# untitled.net
KiCad netlist of a schematic drawn in EAGLE
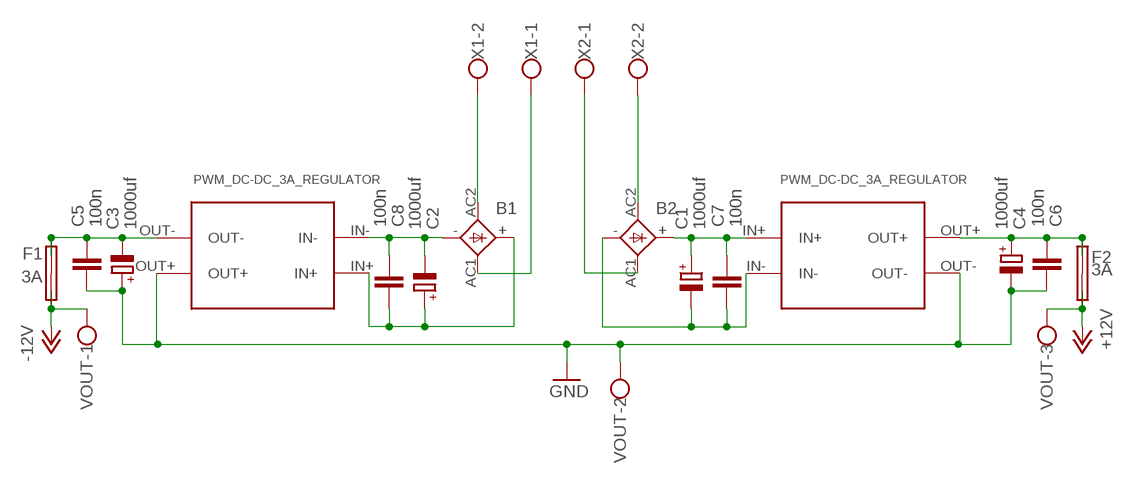
[diagram p0: schematic, sheet 1]
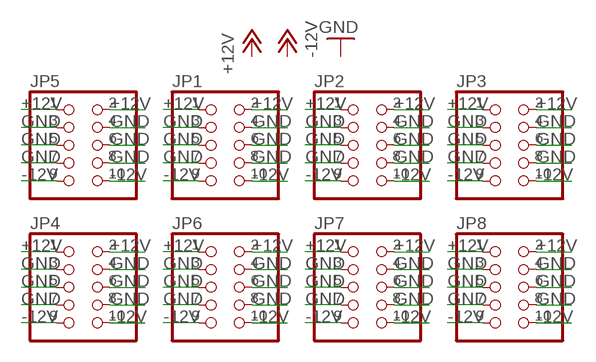
[diagram p1: schematic, sheet 2]

(export (version "E")
  (design (tool "Eeschema 10.0.6"))
  (components
    (comp (ref "B1")
      (value "FB15")
      (footprint "eagle-import:FB15")
      (libsource (lib "eagle-import") (part "FB15"))
    )
    (comp (ref "B2")
      (value "FB15")
      (footprint "eagle-import:FB15")
      (libsource (lib "eagle-import") (part "FB15"))
    )
    (comp (ref "C1")
      (value "1000uf")
      (footprint "eagle-import:TT5D11")
      (libsource (lib "eagle-import") (part "CPOL-EUTT5D11"))
    )
    (comp (ref "C2")
      (value "1000uf")
      (footprint "eagle-import:TT5D11")
      (libsource (lib "eagle-import") (part "CPOL-EUTT5D11"))
    )
    (comp (ref "C3")
      (value "1000uf")
      (footprint "eagle-import:TT5D11")
      (libsource (lib "eagle-import") (part "CPOL-EUTT5D11"))
    )
    (comp (ref "C4")
      (value "1000uf")
      (footprint "eagle-import:TT5D11")
      (libsource (lib "eagle-import") (part "CPOL-EUTT5D11"))
    )
    (comp (ref "C5")
      (value "100n")
      (footprint "eagle-import:C075-032X103")
      (libsource (lib "eagle-import") (part "C-EU075-032X103"))
    )
    (comp (ref "C6")
      (value "100n")
      (footprint "eagle-import:C075-032X103")
      (libsource (lib "eagle-import") (part "C-EU075-032X103"))
    )
    (comp (ref "C7")
      (value "100n")
      (footprint "eagle-import:C075-032X103")
      (libsource (lib "eagle-import") (part "C-EU075-032X103"))
    )
    (comp (ref "C8")
      (value "100n")
      (footprint "eagle-import:C075-032X103")
      (libsource (lib "eagle-import") (part "C-EU075-032X103"))
    )
    (comp (ref "F1")
      (value "3A")
      (footprint "eagle-import:SHK20L")
      (libsource (lib "eagle-import") (part "SHK20L"))
    )
    (comp (ref "F2")
      (value "3A")
      (footprint "eagle-import:SHK20L")
      (libsource (lib "eagle-import") (part "SHK20L"))
    )
    (comp (ref "PWM_DC-DC_3A_REGULATOR1")
      (value "CP8-ADJ")
      (footprint "eagle-import:CP8-ADJ")
      (libsource (lib "eagle-import") (part "CP8-ADJ"))
    )
    (comp (ref "PWM_DC-DC_3A_REGULATOR2")
      (value "CP8-ADJ")
      (footprint "eagle-import:CP8-ADJ")
      (libsource (lib "eagle-import") (part "CP8-ADJ"))
    )
    (comp (ref "VOUT")
      (value "W237-103")
      (footprint "eagle-import:W237-103")
      (fields (field (name "MPN") "237-103"))
      (libsource (lib "eagle-import") (part "W237-103"))
    )
    (comp (ref "X1")
      (value "W237-102")
      (footprint "eagle-import:W237-102")
      (fields (field (name "MPN") "237-102"))
      (libsource (lib "eagle-import") (part "W237-102"))
    )
    (comp (ref "X2")
      (value "W237-102")
      (footprint "eagle-import:W237-102")
      (fields (field (name "MPN") "237-102"))
      (libsource (lib "eagle-import") (part "W237-102"))
    )
    (comp (ref "JP1")
      (value "PINHD-2X5")
      (footprint "eagle-import:2X05")
      (libsource (lib "eagle-import") (part "PINHD-2X5"))
    )
    (comp (ref "JP2")
      (value "PINHD-2X5")
      (footprint "eagle-import:2X05")
      (libsource (lib "eagle-import") (part "PINHD-2X5"))
    )
    (comp (ref "JP3")
      (value "PINHD-2X5")
      (footprint "eagle-import:2X05")
      (libsource (lib "eagle-import") (part "PINHD-2X5"))
    )
    (comp (ref "JP4")
      (value "PINHD-2X5")
      (footprint "eagle-import:2X05")
      (libsource (lib "eagle-import") (part "PINHD-2X5"))
    )
    (comp (ref "JP5")
      (value "PINHD-2X5")
      (footprint "eagle-import:2X05")
      (libsource (lib "eagle-import") (part "PINHD-2X5"))
    )
    (comp (ref "JP6")
      (value "PINHD-2X5")
      (footprint "eagle-import:2X05")
      (libsource (lib "eagle-import") (part "PINHD-2X5"))
    )
    (comp (ref "JP7")
      (value "PINHD-2X5")
      (footprint "eagle-import:2X05")
      (libsource (lib "eagle-import") (part "PINHD-2X5"))
    )
    (comp (ref "JP8")
      (value "PINHD-2X5")
      (footprint "eagle-import:2X05")
      (libsource (lib "eagle-import") (part "PINHD-2X5"))
    )
  )
  (nets
    (net (code "1") (name "+12V") (class "Default")
      (node (ref "F2") (pin "1A") (pinfunction "1A_1A") (pintype "passive"))
      (node (ref "F2") (pin "1B") (pinfunction "1B_1B") (pintype "passive"))
      (node (ref "JP1") (pin "1") (pinfunction "1_1") (pintype "passive"))
      (node (ref "JP1") (pin "2") (pinfunction "2_2") (pintype "passive"))
      (node (ref "JP2") (pin "1") (pinfunction "1_1") (pintype "passive"))
      (node (ref "JP2") (pin "2") (pinfunction "2_2") (pintype "passive"))
      (node (ref "JP3") (pin "1") (pinfunction "1_1") (pintype "passive"))
      (node (ref "JP3") (pin "2") (pinfunction "2_2") (pintype "passive"))
      (node (ref "JP4") (pin "1") (pinfunction "1_1") (pintype "passive"))
      (node (ref "JP4") (pin "2") (pinfunction "2_2") (pintype "passive"))
      (node (ref "JP5") (pin "1") (pinfunction "1_1") (pintype "passive"))
      (node (ref "JP5") (pin "2") (pinfunction "2_2") (pintype "passive"))
      (node (ref "JP6") (pin "1") (pinfunction "1_1") (pintype "passive"))
      (node (ref "JP6") (pin "2") (pinfunction "2_2") (pintype "passive"))
      (node (ref "JP7") (pin "1") (pinfunction "1_1") (pintype "passive"))
      (node (ref "JP7") (pin "2") (pinfunction "2_2") (pintype "passive"))
      (node (ref "JP8") (pin "1") (pinfunction "1_1") (pintype "passive"))
      (node (ref "JP8") (pin "2") (pinfunction "2_2") (pintype "passive"))
      (node (ref "VOUT") (pin "3") (pinfunction "KL_3") (pintype "passive"))
    )
    (net (code "2") (name "-12V") (class "Default")
      (node (ref "F1") (pin "1A") (pinfunction "1A_1A") (pintype "passive"))
      (node (ref "F1") (pin "1B") (pinfunction "1B_1B") (pintype "passive"))
      (node (ref "JP1") (pin "10") (pinfunction "10_10") (pintype "passive"))
      (node (ref "JP1") (pin "9") (pinfunction "9_9") (pintype "passive"))
      (node (ref "JP2") (pin "10") (pinfunction "10_10") (pintype "passive"))
      (node (ref "JP2") (pin "9") (pinfunction "9_9") (pintype "passive"))
      (node (ref "JP3") (pin "10") (pinfunction "10_10") (pintype "passive"))
      (node (ref "JP3") (pin "9") (pinfunction "9_9") (pintype "passive"))
      (node (ref "JP4") (pin "10") (pinfunction "10_10") (pintype "passive"))
      (node (ref "JP4") (pin "9") (pinfunction "9_9") (pintype "passive"))
      (node (ref "JP5") (pin "10") (pinfunction "10_10") (pintype "passive"))
      (node (ref "JP5") (pin "9") (pinfunction "9_9") (pintype "passive"))
      (node (ref "JP6") (pin "10") (pinfunction "10_10") (pintype "passive"))
      (node (ref "JP6") (pin "9") (pinfunction "9_9") (pintype "passive"))
      (node (ref "JP7") (pin "10") (pinfunction "10_10") (pintype "passive"))
      (node (ref "JP7") (pin "9") (pinfunction "9_9") (pintype "passive"))
      (node (ref "JP8") (pin "10") (pinfunction "10_10") (pintype "passive"))
      (node (ref "JP8") (pin "9") (pinfunction "9_9") (pintype "passive"))
      (node (ref "VOUT") (pin "1") (pinfunction "KL_1") (pintype "passive"))
    )
    (net (code "3") (name "GND") (class "Default")
      (node (ref "C3") (pin "+") (pinfunction "+_+") (pintype "passive"))
      (node (ref "C4") (pin "-") (pinfunction "-_-") (pintype "passive"))
      (node (ref "C5") (pin "2") (pinfunction "2_2") (pintype "passive"))
      (node (ref "C6") (pin "1") (pinfunction "1_1") (pintype "passive"))
      (node (ref "JP1") (pin "3") (pinfunction "3_3") (pintype "passive"))
      (node (ref "JP1") (pin "4") (pinfunction "4_4") (pintype "passive"))
      (node (ref "JP1") (pin "5") (pinfunction "5_5") (pintype "passive"))
      (node (ref "JP1") (pin "6") (pinfunction "6_6") (pintype "passive"))
      (node (ref "JP1") (pin "7") (pinfunction "7_7") (pintype "passive"))
      (node (ref "JP1") (pin "8") (pinfunction "8_8") (pintype "passive"))
      (node (ref "JP2") (pin "3") (pinfunction "3_3") (pintype "passive"))
      (node (ref "JP2") (pin "4") (pinfunction "4_4") (pintype "passive"))
      (node (ref "JP2") (pin "5") (pinfunction "5_5") (pintype "passive"))
      (node (ref "JP2") (pin "6") (pinfunction "6_6") (pintype "passive"))
      (node (ref "JP2") (pin "7") (pinfunction "7_7") (pintype "passive"))
      (node (ref "JP2") (pin "8") (pinfunction "8_8") (pintype "passive"))
      (node (ref "JP3") (pin "3") (pinfunction "3_3") (pintype "passive"))
      (node (ref "JP3") (pin "4") (pinfunction "4_4") (pintype "passive"))
      (node (ref "JP3") (pin "5") (pinfunction "5_5") (pintype "passive"))
      (node (ref "JP3") (pin "6") (pinfunction "6_6") (pintype "passive"))
      (node (ref "JP3") (pin "7") (pinfunction "7_7") (pintype "passive"))
      (node (ref "JP3") (pin "8") (pinfunction "8_8") (pintype "passive"))
      (node (ref "JP4") (pin "3") (pinfunction "3_3") (pintype "passive"))
      (node (ref "JP4") (pin "4") (pinfunction "4_4") (pintype "passive"))
      (node (ref "JP4") (pin "5") (pinfunction "5_5") (pintype "passive"))
      (node (ref "JP4") (pin "6") (pinfunction "6_6") (pintype "passive"))
      (node (ref "JP4") (pin "7") (pinfunction "7_7") (pintype "passive"))
      (node (ref "JP4") (pin "8") (pinfunction "8_8") (pintype "passive"))
      (node (ref "JP5") (pin "3") (pinfunction "3_3") (pintype "passive"))
      (node (ref "JP5") (pin "4") (pinfunction "4_4") (pintype "passive"))
      (node (ref "JP5") (pin "5") (pinfunction "5_5") (pintype "passive"))
      (node (ref "JP5") (pin "6") (pinfunction "6_6") (pintype "passive"))
      (node (ref "JP5") (pin "7") (pinfunction "7_7") (pintype "passive"))
      (node (ref "JP5") (pin "8") (pinfunction "8_8") (pintype "passive"))
      (node (ref "JP6") (pin "3") (pinfunction "3_3") (pintype "passive"))
      (node (ref "JP6") (pin "4") (pinfunction "4_4") (pintype "passive"))
      (node (ref "JP6") (pin "5") (pinfunction "5_5") (pintype "passive"))
      (node (ref "JP6") (pin "6") (pinfunction "6_6") (pintype "passive"))
      (node (ref "JP6") (pin "7") (pinfunction "7_7") (pintype "passive"))
      (node (ref "JP6") (pin "8") (pinfunction "8_8") (pintype "passive"))
      (node (ref "JP7") (pin "3") (pinfunction "3_3") (pintype "passive"))
      (node (ref "JP7") (pin "4") (pinfunction "4_4") (pintype "passive"))
      (node (ref "JP7") (pin "5") (pinfunction "5_5") (pintype "passive"))
      (node (ref "JP7") (pin "6") (pinfunction "6_6") (pintype "passive"))
      (node (ref "JP7") (pin "7") (pinfunction "7_7") (pintype "passive"))
      (node (ref "JP7") (pin "8") (pinfunction "8_8") (pintype "passive"))
      (node (ref "JP8") (pin "3") (pinfunction "3_3") (pintype "passive"))
      (node (ref "JP8") (pin "4") (pinfunction "4_4") (pintype "passive"))
      (node (ref "JP8") (pin "5") (pinfunction "5_5") (pintype "passive"))
      (node (ref "JP8") (pin "6") (pinfunction "6_6") (pintype "passive"))
      (node (ref "JP8") (pin "7") (pinfunction "7_7") (pintype "passive"))
      (node (ref "JP8") (pin "8") (pinfunction "8_8") (pintype "passive"))
      (node (ref "PWM_DC-DC_3A_REGULATOR1") (pin "OUT+") (pinfunction "OUT+_OUT+") (pintype "passive"))
      (node (ref "PWM_DC-DC_3A_REGULATOR2") (pin "OUT-") (pinfunction "OUT-_OUT-") (pintype "passive"))
      (node (ref "VOUT") (pin "2") (pinfunction "KL_2") (pintype "passive"))
    )
    (net (code "4") (name "Net-(B1-Pad+)") (class "Default")
      (node (ref "B1") (pin "+") (pinfunction "+_+") (pintype "passive"))
      (node (ref "C2") (pin "+") (pinfunction "+_+") (pintype "passive"))
      (node (ref "C8") (pin "1") (pinfunction "1_1") (pintype "passive"))
      (node (ref "PWM_DC-DC_3A_REGULATOR1") (pin "IN+") (pinfunction "IN+_IN+") (pintype "passive"))
    )
    (net (code "5") (name "Net-(B1-Pad-)") (class "Default")
      (node (ref "B1") (pin "-") (pinfunction "-_-") (pintype "passive"))
      (node (ref "C2") (pin "-") (pinfunction "-_-") (pintype "passive"))
      (node (ref "C8") (pin "2") (pinfunction "2_2") (pintype "passive"))
      (node (ref "PWM_DC-DC_3A_REGULATOR1") (pin "IN-") (pinfunction "IN-_IN-") (pintype "passive"))
    )
    (net (code "6") (name "Net-(B2-Pad+)") (class "Default")
      (node (ref "B2") (pin "+") (pinfunction "+_+") (pintype "passive"))
      (node (ref "C1") (pin "+") (pinfunction "+_+") (pintype "passive"))
      (node (ref "C7") (pin "2") (pinfunction "2_2") (pintype "passive"))
      (node (ref "PWM_DC-DC_3A_REGULATOR2") (pin "IN+") (pinfunction "IN+_IN+") (pintype "passive"))
    )
    (net (code "7") (name "Net-(B2-Pad-)") (class "Default")
      (node (ref "B2") (pin "-") (pinfunction "-_-") (pintype "passive"))
      (node (ref "C1") (pin "-") (pinfunction "-_-") (pintype "passive"))
      (node (ref "C7") (pin "1") (pinfunction "1_1") (pintype "passive"))
      (node (ref "PWM_DC-DC_3A_REGULATOR2") (pin "IN-") (pinfunction "IN-_IN-") (pintype "passive"))
    )
    (net (code "8") (name "Net-(C3-Pad-)") (class "Default")
      (node (ref "C3") (pin "-") (pinfunction "-_-") (pintype "passive"))
      (node (ref "C5") (pin "1") (pinfunction "1_1") (pintype "passive"))
      (node (ref "F1") (pin "2A") (pinfunction "2A_2A") (pintype "passive"))
      (node (ref "F1") (pin "2B") (pinfunction "2B_2B") (pintype "passive"))
      (node (ref "PWM_DC-DC_3A_REGULATOR1") (pin "OUT-") (pinfunction "OUT-_OUT-") (pintype "passive"))
    )
    (net (code "9") (name "Net-(C4-Pad+)") (class "Default")
      (node (ref "C4") (pin "+") (pinfunction "+_+") (pintype "passive"))
      (node (ref "C6") (pin "2") (pinfunction "2_2") (pintype "passive"))
      (node (ref "F2") (pin "2A") (pinfunction "2A_2A") (pintype "passive"))
      (node (ref "F2") (pin "2B") (pinfunction "2B_2B") (pintype "passive"))
      (node (ref "PWM_DC-DC_3A_REGULATOR2") (pin "OUT+") (pinfunction "OUT+_OUT+") (pintype "passive"))
    )
    (net (code "10") (name "Net-(X1A-KL)") (class "Default")
      (node (ref "B1") (pin "AC1") (pinfunction "AC1_AC1") (pintype "passive"))
      (node (ref "X1") (pin "1") (pinfunction "KL_1") (pintype "passive"))
    )
    (net (code "11") (name "Net-(X1B-KL)") (class "Default")
      (node (ref "B1") (pin "AC2") (pinfunction "AC2_AC2") (pintype "passive"))
      (node (ref "X1") (pin "2") (pinfunction "KL_2") (pintype "passive"))
    )
    (net (code "12") (name "Net-(X2A-KL)") (class "Default")
      (node (ref "B2") (pin "AC1") (pinfunction "AC1_AC1") (pintype "passive"))
      (node (ref "X2") (pin "1") (pinfunction "KL_1") (pintype "passive"))
    )
    (net (code "13") (name "Net-(X2B-KL)") (class "Default")
      (node (ref "B2") (pin "AC2") (pinfunction "AC2_AC2") (pintype "passive"))
      (node (ref "X2") (pin "2") (pinfunction "KL_2") (pintype "passive"))
    )
  )
)
